# Schematic.net
KiCad netlist of a schematic drawn in EAGLE
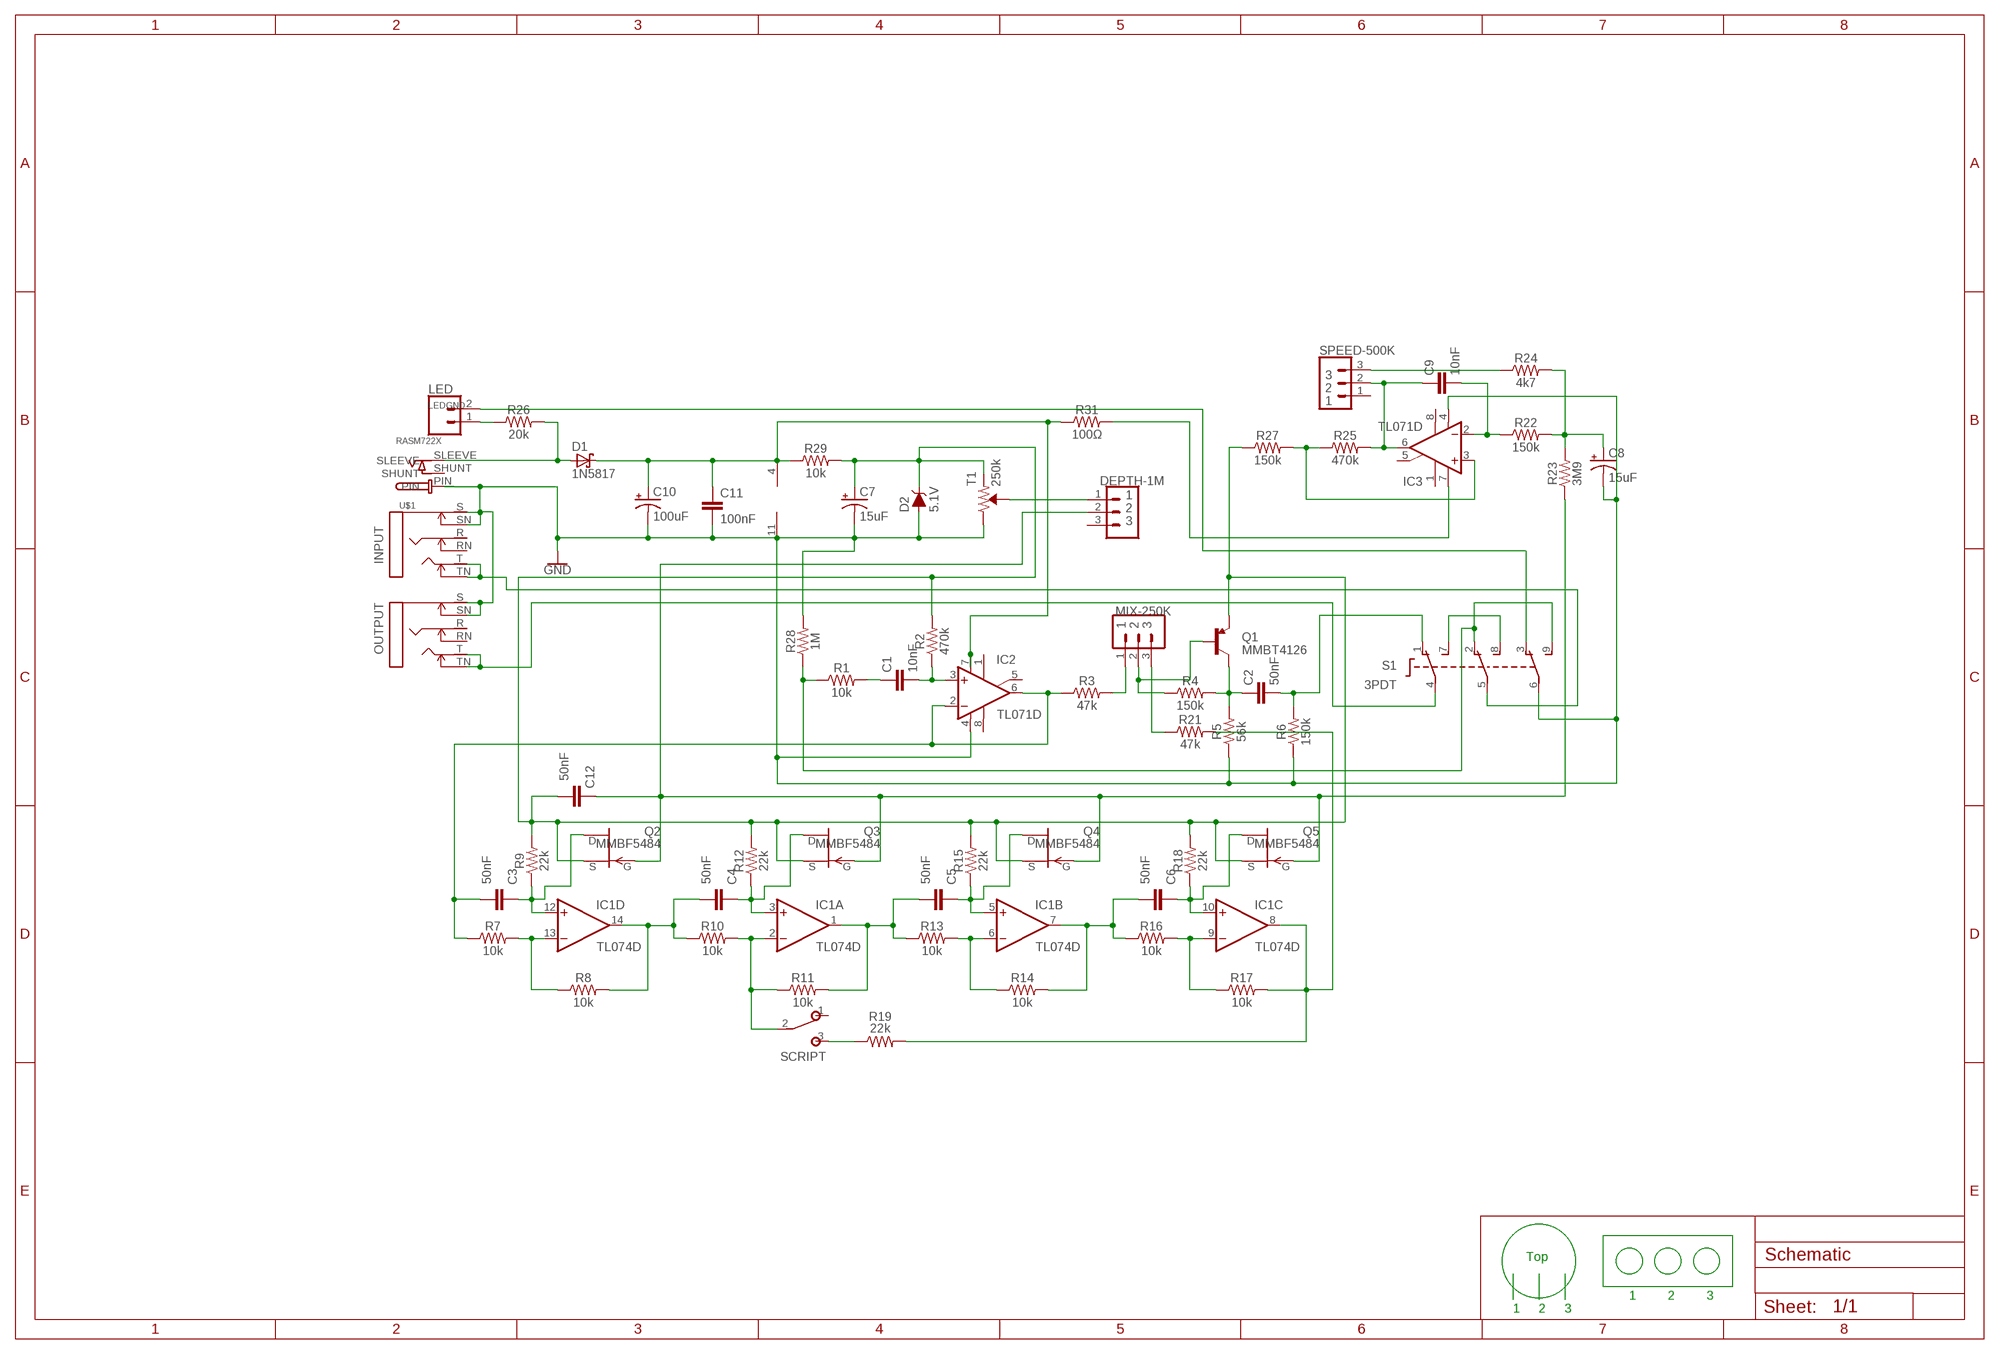
[diagram p0: schematic, sheet 1]

(export (version "E")
  (design (tool "Eeschema 10.0.6"))
  (components
    (comp (ref "C1")
      (value "10nF")
      (footprint "eagle-import:0603")
      (libsource (lib "eagle-import") (part "0.1UF-0603-25V-(+80/-20%)"))
    )
    (comp (ref "C2")
      (value "50nF")
      (footprint "eagle-import:0603")
      (libsource (lib "eagle-import") (part "0.1UF-0603-25V-(+80/-20%)"))
    )
    (comp (ref "C3")
      (value "50nF")
      (footprint "eagle-import:0603")
      (libsource (lib "eagle-import") (part "10NF-0603-50V-10%"))
    )
    (comp (ref "C4")
      (value "50nF")
      (footprint "eagle-import:0603")
      (libsource (lib "eagle-import") (part "10NF-0603-50V-10%"))
    )
    (comp (ref "C5")
      (value "50nF")
      (footprint "eagle-import:0603")
      (libsource (lib "eagle-import") (part "10NF-0603-50V-10%"))
    )
    (comp (ref "C6")
      (value "50nF")
      (footprint "eagle-import:0603")
      (libsource (lib "eagle-import") (part "10NF-0603-50V-10%"))
    )
    (comp (ref "C7")
      (value "15uF")
      (footprint "eagle-import:EIA7343")
      (libsource (lib "eagle-import") (part "100UF-POLAR-EIA7343-10V-10%(TANT)"))
    )
    (comp (ref "C8")
      (value "15uF")
      (footprint "eagle-import:EIA7343")
      (libsource (lib "eagle-import") (part "100UF-POLAR-EIA7343-10V-10%(TANT)"))
    )
    (comp (ref "C9")
      (value "10nF")
      (footprint "eagle-import:0603")
      (libsource (lib "eagle-import") (part "0.1UF-0603-25V-(+80/-20%)"))
    )
    (comp (ref "C10")
      (value "100uF")
      (footprint "eagle-import:EIA7343")
      (libsource (lib "eagle-import") (part "100UF-POLAR-EIA7343-10V-10%(TANT)"))
    )
    (comp (ref "C11")
      (value "100nF")
      (footprint "eagle-import:0603")
      (libsource (lib "eagle-import") (part "0.1UF-0603-25V-(+80/-20%)"))
    )
    (comp (ref "C12")
      (value "50nF")
      (footprint "eagle-import:0603")
      (libsource (lib "eagle-import") (part "10NF-0603-50V-10%"))
    )
    (comp (ref "D1")
      (value "1N5817")
      (footprint "eagle-import:DO41-7.6")
      (libsource (lib "eagle-import") (part "1N5817-T"))
    )
    (comp (ref "D2")
      (value "5.1V")
      (footprint "eagle-import:SOD-323")
      (libsource (lib "eagle-import") (part "DIODE-ZENER-BZT52C3V6S"))
    )
    (comp (ref "DEPTH-1M")
      (value "CONN_03")
      (footprint "eagle-import:1X03")
      (libsource (lib "eagle-import") (part "CONN_03"))
    )
    (comp (ref "IC1")
      (value "TL074D")
      (footprint "eagle-import:SO14")
      (libsource (lib "eagle-import") (part "TL074D"))
    )
    (comp (ref "IC2")
      (value "TL071D")
      (footprint "eagle-import:SO08")
      (libsource (lib "eagle-import") (part "TL071D"))
    )
    (comp (ref "IC3")
      (value "TL071D")
      (footprint "eagle-import:SO08")
      (libsource (lib "eagle-import") (part "TL071D"))
    )
    (comp (ref "INPUT")
      (value "STEREOSW")
      (footprint "eagle-import:NMJ6HCD2")
      (libsource (lib "eagle-import") (part "STEREOSW"))
    )
    (comp (ref "LED")
      (value "CONN_02")
      (footprint "eagle-import:1X02")
      (libsource (lib "eagle-import") (part "CONN_02"))
    )
    (comp (ref "MIX-250K")
      (value "CONN_03")
      (footprint "eagle-import:1X03")
      (libsource (lib "eagle-import") (part "CONN_03"))
    )
    (comp (ref "OUTPUT")
      (value "STEREOSW")
      (footprint "eagle-import:NMJ6HCD2")
      (libsource (lib "eagle-import") (part "STEREOSW"))
    )
    (comp (ref "Q1")
      (value "MMBT4126")
      (footprint "eagle-import:SOT23-3")
      (libsource (lib "eagle-import") (part "TRANSISTOR_PNPMMBT4403"))
    )
    (comp (ref "Q2")
      (value "MMBF5484")
      (footprint "eagle-import:SOT23")
      (libsource (lib "eagle-import") (part "?548SST4"))
    )
    (comp (ref "Q3")
      (value "MMBF5484")
      (footprint "eagle-import:SOT23")
      (libsource (lib "eagle-import") (part "?548SST4"))
    )
    (comp (ref "Q4")
      (value "MMBF5484")
      (footprint "eagle-import:SOT23")
      (libsource (lib "eagle-import") (part "?548SST4"))
    )
    (comp (ref "Q5")
      (value "MMBF5484")
      (footprint "eagle-import:SOT23")
      (libsource (lib "eagle-import") (part "?548SST4"))
    )
    (comp (ref "R1")
      (value "10k")
      (footprint "eagle-import:0603")
      (libsource (lib "eagle-import") (part "10KOHM-0603-1/10W-1%"))
    )
    (comp (ref "R2")
      (value "470k")
      (footprint "eagle-import:0603")
      (libsource (lib "eagle-import") (part "22KOHM-0603-1/10W-1%"))
    )
    (comp (ref "R3")
      (value "47k")
      (footprint "eagle-import:0603")
      (libsource (lib "eagle-import") (part "10KOHM-0603-1/10W-1%"))
    )
    (comp (ref "R4")
      (value "150k")
      (footprint "eagle-import:0603")
      (libsource (lib "eagle-import") (part "10KOHM-0603-1/10W-1%"))
    )
    (comp (ref "R5")
      (value "56k")
      (footprint "eagle-import:0603")
      (libsource (lib "eagle-import") (part "22KOHM-0603-1/10W-1%"))
    )
    (comp (ref "R6")
      (value "150k")
      (footprint "eagle-import:0603")
      (libsource (lib "eagle-import") (part "22KOHM-0603-1/10W-1%"))
    )
    (comp (ref "R7")
      (value "10k")
      (footprint "eagle-import:0603")
      (libsource (lib "eagle-import") (part "10KOHM-0603-1/10W-1%"))
    )
    (comp (ref "R8")
      (value "10k")
      (footprint "eagle-import:0603")
      (libsource (lib "eagle-import") (part "10KOHM-0603-1/10W-1%"))
    )
    (comp (ref "R9")
      (value "22k")
      (footprint "eagle-import:0603")
      (libsource (lib "eagle-import") (part "22KOHM-0603-1/10W-1%"))
    )
    (comp (ref "R10")
      (value "10k")
      (footprint "eagle-import:0603")
      (libsource (lib "eagle-import") (part "10KOHM-0603-1/10W-1%"))
    )
    (comp (ref "R11")
      (value "10k")
      (footprint "eagle-import:0603")
      (libsource (lib "eagle-import") (part "10KOHM-0603-1/10W-1%"))
    )
    (comp (ref "R12")
      (value "22k")
      (footprint "eagle-import:0603")
      (libsource (lib "eagle-import") (part "22KOHM-0603-1/10W-1%"))
    )
    (comp (ref "R13")
      (value "10k")
      (footprint "eagle-import:0603")
      (libsource (lib "eagle-import") (part "10KOHM-0603-1/10W-1%"))
    )
    (comp (ref "R14")
      (value "10k")
      (footprint "eagle-import:0603")
      (libsource (lib "eagle-import") (part "10KOHM-0603-1/10W-1%"))
    )
    (comp (ref "R15")
      (value "22k")
      (footprint "eagle-import:0603")
      (libsource (lib "eagle-import") (part "22KOHM-0603-1/10W-1%"))
    )
    (comp (ref "R16")
      (value "10k")
      (footprint "eagle-import:0603")
      (libsource (lib "eagle-import") (part "10KOHM-0603-1/10W-1%"))
    )
    (comp (ref "R17")
      (value "10k")
      (footprint "eagle-import:0603")
      (libsource (lib "eagle-import") (part "10KOHM-0603-1/10W-1%"))
    )
    (comp (ref "R18")
      (value "22k")
      (footprint "eagle-import:0603")
      (libsource (lib "eagle-import") (part "22KOHM-0603-1/10W-1%"))
    )
    (comp (ref "R19")
      (value "22k")
      (footprint "eagle-import:0603")
      (libsource (lib "eagle-import") (part "10KOHM-0603-1/10W-1%"))
    )
    (comp (ref "R21")
      (value "47k")
      (footprint "eagle-import:0603")
      (libsource (lib "eagle-import") (part "10KOHM-0603-1/10W-1%"))
    )
    (comp (ref "R22")
      (value "150k")
      (footprint "eagle-import:0603")
      (libsource (lib "eagle-import") (part "10KOHM-0603-1/10W-1%"))
    )
    (comp (ref "R23")
      (value "3M9")
      (footprint "eagle-import:0603")
      (libsource (lib "eagle-import") (part "10KOHM-0603-1/10W-1%"))
    )
    (comp (ref "R24")
      (value "4k7")
      (footprint "eagle-import:0603")
      (libsource (lib "eagle-import") (part "10KOHM-0603-1/10W-1%"))
    )
    (comp (ref "R25")
      (value "470k")
      (footprint "eagle-import:0603")
      (libsource (lib "eagle-import") (part "10KOHM-0603-1/10W-1%"))
    )
    (comp (ref "R26")
      (value "20k")
      (footprint "eagle-import:0603")
      (libsource (lib "eagle-import") (part "10KOHM-0603-1/10W-1%"))
    )
    (comp (ref "R27")
      (value "150k")
      (footprint "eagle-import:0603")
      (libsource (lib "eagle-import") (part "10KOHM-0603-1/10W-1%"))
    )
    (comp (ref "R28")
      (value "1M")
      (footprint "eagle-import:0603")
      (libsource (lib "eagle-import") (part "10KOHM-0603-1/10W-1%"))
    )
    (comp (ref "R29")
      (value "10k")
      (footprint "eagle-import:0603")
      (libsource (lib "eagle-import") (part "10KOHM-0603-1/10W-1%"))
    )
    (comp (ref "R31")
      (value "100Ω")
      (footprint "eagle-import:0603")
      (libsource (lib "eagle-import") (part "10KOHM-0603-1/10W-1%"))
    )
    (comp (ref "S1")
      (value "3PDT")
      (footprint "eagle-import:3PDT")
      (libsource (lib "eagle-import") (part "3PDT"))
    )
    (comp (ref "SCRIPT")
      (value "SPDT")
      (footprint "eagle-import:M9040P")
      (libsource (lib "eagle-import") (part "SPDT"))
    )
    (comp (ref "SPEED-500K")
      (value "CONN_03")
      (footprint "eagle-import:1X03")
      (libsource (lib "eagle-import") (part "CONN_03"))
    )
    (comp (ref "T1")
      (value "250k")
      (footprint "eagle-import:TRIMPOT-SMD-3MM-CLOSED")
      (libsource (lib "eagle-import") (part "TRIMPOT-SMD-3MM-CLOSED-1/8W-20%"))
    )
    (comp (ref "U$1")
      (value "RASM722X")
      (footprint "eagle-import:SWITCHCRAFT_RASM722X")
      (fields (field (name "MF") "Switchcraft"))
      (libsource (lib "eagle-import") (part "RASM722X"))
    )
  )
  (nets
    (net (code "1") (name "/1") (class "Default")
      (node (ref "MIX-250K") (pin "1") (pinfunction "1_1") (pintype "passive"))
      (node (ref "R3") (pin "2") (pinfunction "2_2") (pintype "passive"))
    )
    (net (code "2") (name "/2") (class "Default")
      (node (ref "C9") (pin "1") (pinfunction "1_1") (pintype "passive"))
      (node (ref "IC3") (pin "6") (pinfunction "OUT_6") (pintype "output"))
      (node (ref "R25") (pin "2") (pinfunction "2_2") (pintype "passive"))
      (node (ref "SPEED-500K") (pin "2") (pinfunction "2_2") (pintype "passive"))
    )
    (net (code "3") (name "/3") (class "Default")
      (node (ref "R24") (pin "1") (pinfunction "1_1") (pintype "passive"))
      (node (ref "SPEED-500K") (pin "3") (pinfunction "3_3") (pintype "passive"))
    )
    (net (code "4") (name "/LEDGND") (class "Default")
      (node (ref "LED") (pin "2") (pinfunction "2_2") (pintype "passive"))
      (node (ref "S1") (pin "3") (pinfunction "O3_3") (pintype "passive"))
    )
    (net (code "6") (name "/SHUNT") (class "Default")
      (node (ref "U$1") (pin "SHUNT") (pinfunction "SHUNT_SHUNT") (pintype "power_in"))
    )
    (net (code "7") (name "GND") (class "Default")
      (node (ref "C10") (pin "C") (pinfunction "-_C") (pintype "passive"))
      (node (ref "C11") (pin "2") (pinfunction "2_2") (pintype "passive"))
      (node (ref "C7") (pin "C") (pinfunction "-_C") (pintype "passive"))
      (node (ref "C8") (pin "C") (pinfunction "-_C") (pintype "passive"))
      (node (ref "D2") (pin "A") (pinfunction "A_A") (pintype "passive"))
      (node (ref "IC1") (pin "11") (pinfunction "V-_11") (pintype "power_in"))
      (node (ref "IC2") (pin "4") (pinfunction "V-_4") (pintype "power_in"))
      (node (ref "IC3") (pin "4") (pinfunction "V-_4") (pintype "power_in"))
      (node (ref "INPUT") (pin "S") (pinfunction "S_S") (pintype "passive"))
      (node (ref "INPUT") (pin "SN") (pinfunction "SN_SN") (pintype "passive"))
      (node (ref "OUTPUT") (pin "S") (pinfunction "S_S") (pintype "passive"))
      (node (ref "OUTPUT") (pin "SN") (pinfunction "SN_SN") (pintype "passive"))
      (node (ref "R28") (pin "2") (pinfunction "2_2") (pintype "passive"))
      (node (ref "R5") (pin "1") (pinfunction "1_1") (pintype "passive"))
      (node (ref "R6") (pin "1") (pinfunction "1_1") (pintype "passive"))
      (node (ref "S1") (pin "6") (pinfunction "P3_6") (pintype "passive"))
      (node (ref "T1") (pin "3") (pinfunction "CW_3") (pintype "passive"))
      (node (ref "U$1") (pin "PIN") (pinfunction "PIN_PIN") (pintype "bidirectional"))
    )
    (net (code "8") (name "Net-(C1-Pad1)") (class "Default")
      (node (ref "C1") (pin "1") (pinfunction "1_1") (pintype "passive"))
      (node (ref "R1") (pin "2") (pinfunction "2_2") (pintype "passive"))
    )
    (net (code "9") (name "Net-(C7-+)") (class "Default")
      (node (ref "C12") (pin "2") (pinfunction "2_2") (pintype "passive"))
      (node (ref "C7") (pin "A") (pinfunction "+_A") (pintype "passive"))
      (node (ref "D2") (pin "C") (pinfunction "C_C") (pintype "passive"))
      (node (ref "Q1") (pin "2") (pinfunction "E_2") (pintype "passive"))
      (node (ref "Q2") (pin "2") (pinfunction "S_2") (pintype "passive"))
      (node (ref "Q3") (pin "2") (pinfunction "S_2") (pintype "passive"))
      (node (ref "Q4") (pin "2") (pinfunction "S_2") (pintype "passive"))
      (node (ref "Q5") (pin "2") (pinfunction "S_2") (pintype "passive"))
      (node (ref "R12") (pin "2") (pinfunction "2_2") (pintype "passive"))
      (node (ref "R15") (pin "2") (pinfunction "2_2") (pintype "passive"))
      (node (ref "R18") (pin "2") (pinfunction "2_2") (pintype "passive"))
      (node (ref "R2") (pin "2") (pinfunction "2_2") (pintype "passive"))
      (node (ref "R27") (pin "1") (pinfunction "1_1") (pintype "passive"))
      (node (ref "R29") (pin "2") (pinfunction "2_2") (pintype "passive"))
      (node (ref "R9") (pin "2") (pinfunction "2_2") (pintype "passive"))
      (node (ref "T1") (pin "1") (pinfunction "CCW_1") (pintype "passive"))
    )
    (net (code "10") (name "Net-(C8-+)") (class "Default")
      (node (ref "C8") (pin "A") (pinfunction "+_A") (pintype "passive"))
      (node (ref "R22") (pin "2") (pinfunction "2_2") (pintype "passive"))
      (node (ref "R23") (pin "2") (pinfunction "2_2") (pintype "passive"))
      (node (ref "R24") (pin "2") (pinfunction "2_2") (pintype "passive"))
    )
    (net (code "11") (name "Net-(C10-+)") (class "Default")
      (node (ref "C10") (pin "A") (pinfunction "+_A") (pintype "passive"))
      (node (ref "C11") (pin "1") (pinfunction "1_1") (pintype "passive"))
      (node (ref "D1") (pin "C") (pinfunction "C_C") (pintype "passive"))
      (node (ref "IC1") (pin "4") (pinfunction "V+_4") (pintype "power_in"))
      (node (ref "IC2") (pin "7") (pinfunction "V+_7") (pintype "power_in"))
      (node (ref "R29") (pin "1") (pinfunction "1_1") (pintype "passive"))
      (node (ref "R31") (pin "1") (pinfunction "1_1") (pintype "passive"))
    )
    (net (code "12") (name "Net-(D1-PadA)") (class "Default")
      (node (ref "D1") (pin "A") (pinfunction "A_A") (pintype "passive"))
      (node (ref "R26") (pin "2") (pinfunction "2_2") (pintype "passive"))
      (node (ref "U$1") (pin "SLEEVE") (pinfunction "SLEEVE_SLEEVE") (pintype "power_in"))
    )
    (net (code "13") (name "Net-(IC1A-+IN)") (class "Default")
      (node (ref "C4") (pin "1") (pinfunction "1_1") (pintype "passive"))
      (node (ref "IC1") (pin "3") (pinfunction "+IN_3") (pintype "input"))
      (node (ref "Q3") (pin "1") (pinfunction "D_1") (pintype "passive"))
      (node (ref "R12") (pin "1") (pinfunction "1_1") (pintype "passive"))
    )
    (net (code "14") (name "Net-(IC1A--IN)") (class "Default")
      (node (ref "IC1") (pin "2") (pinfunction "-IN_2") (pintype "input"))
      (node (ref "R10") (pin "2") (pinfunction "2_2") (pintype "passive"))
      (node (ref "R11") (pin "1") (pinfunction "1_1") (pintype "passive"))
      (node (ref "SCRIPT") (pin "2") (pinfunction "P_2") (pintype "passive"))
    )
    (net (code "15") (name "Net-(IC1A-OUT)") (class "Default")
      (node (ref "C5") (pin "2") (pinfunction "2_2") (pintype "passive"))
      (node (ref "IC1") (pin "1") (pinfunction "OUT_1") (pintype "output"))
      (node (ref "R11") (pin "2") (pinfunction "2_2") (pintype "passive"))
      (node (ref "R13") (pin "1") (pinfunction "1_1") (pintype "passive"))
    )
    (net (code "16") (name "Net-(IC1B-+IN)") (class "Default")
      (node (ref "C5") (pin "1") (pinfunction "1_1") (pintype "passive"))
      (node (ref "IC1") (pin "5") (pinfunction "+IN_5") (pintype "input"))
      (node (ref "Q4") (pin "1") (pinfunction "D_1") (pintype "passive"))
      (node (ref "R15") (pin "1") (pinfunction "1_1") (pintype "passive"))
    )
    (net (code "17") (name "Net-(IC1B--IN)") (class "Default")
      (node (ref "IC1") (pin "6") (pinfunction "-IN_6") (pintype "input"))
      (node (ref "R13") (pin "2") (pinfunction "2_2") (pintype "passive"))
      (node (ref "R14") (pin "1") (pinfunction "1_1") (pintype "passive"))
    )
    (net (code "18") (name "Net-(IC1B-OUT)") (class "Default")
      (node (ref "C6") (pin "2") (pinfunction "2_2") (pintype "passive"))
      (node (ref "IC1") (pin "7") (pinfunction "OUT_7") (pintype "output"))
      (node (ref "R14") (pin "2") (pinfunction "2_2") (pintype "passive"))
      (node (ref "R16") (pin "1") (pinfunction "1_1") (pintype "passive"))
    )
    (net (code "19") (name "Net-(IC1C-+IN)") (class "Default")
      (node (ref "C6") (pin "1") (pinfunction "1_1") (pintype "passive"))
      (node (ref "IC1") (pin "10") (pinfunction "+IN_10") (pintype "input"))
      (node (ref "Q5") (pin "1") (pinfunction "D_1") (pintype "passive"))
      (node (ref "R18") (pin "1") (pinfunction "1_1") (pintype "passive"))
    )
    (net (code "20") (name "Net-(IC1C--IN)") (class "Default")
      (node (ref "IC1") (pin "9") (pinfunction "-IN_9") (pintype "input"))
      (node (ref "R16") (pin "2") (pinfunction "2_2") (pintype "passive"))
      (node (ref "R17") (pin "1") (pinfunction "1_1") (pintype "passive"))
    )
    (net (code "21") (name "Net-(IC1C-OUT)") (class "Default")
      (node (ref "IC1") (pin "8") (pinfunction "OUT_8") (pintype "output"))
      (node (ref "R17") (pin "2") (pinfunction "2_2") (pintype "passive"))
      (node (ref "R19") (pin "2") (pinfunction "2_2") (pintype "passive"))
      (node (ref "R21") (pin "2") (pinfunction "2_2") (pintype "passive"))
    )
    (net (code "22") (name "Net-(IC1D-+IN)") (class "Default")
      (node (ref "C3") (pin "1") (pinfunction "1_1") (pintype "passive"))
      (node (ref "IC1") (pin "12") (pinfunction "+IN_12") (pintype "input"))
      (node (ref "Q2") (pin "1") (pinfunction "D_1") (pintype "passive"))
      (node (ref "R9") (pin "1") (pinfunction "1_1") (pintype "passive"))
    )
    (net (code "23") (name "Net-(IC1D--IN)") (class "Default")
      (node (ref "IC1") (pin "13") (pinfunction "-IN_13") (pintype "input"))
      (node (ref "R7") (pin "2") (pinfunction "2_2") (pintype "passive"))
      (node (ref "R8") (pin "1") (pinfunction "1_1") (pintype "passive"))
    )
    (net (code "24") (name "Net-(IC1D-OUT)") (class "Default")
      (node (ref "C4") (pin "2") (pinfunction "2_2") (pintype "passive"))
      (node (ref "IC1") (pin "14") (pinfunction "OUT_14") (pintype "output"))
      (node (ref "R10") (pin "1") (pinfunction "1_1") (pintype "passive"))
      (node (ref "R8") (pin "2") (pinfunction "2_2") (pintype "passive"))
    )
    (net (code "25") (name "Net-(IC2-+IN)") (class "Default")
      (node (ref "C1") (pin "2") (pinfunction "2_2") (pintype "passive"))
      (node (ref "IC2") (pin "3") (pinfunction "+IN_3") (pintype "input"))
      (node (ref "R2") (pin "1") (pinfunction "1_1") (pintype "passive"))
    )
    (net (code "26") (name "Net-(IC2--IN)") (class "Default")
      (node (ref "C3") (pin "2") (pinfunction "2_2") (pintype "passive"))
      (node (ref "IC2") (pin "2") (pinfunction "-IN_2") (pintype "input"))
      (node (ref "IC2") (pin "6") (pinfunction "OUT_6") (pintype "output"))
      (node (ref "R3") (pin "1") (pinfunction "1_1") (pintype "passive"))
      (node (ref "R7") (pin "1") (pinfunction "1_1") (pintype "passive"))
    )
    (net (code "27") (name "Net-(IC3-+IN)") (class "Default")
      (node (ref "IC3") (pin "3") (pinfunction "+IN_3") (pintype "input"))
      (node (ref "R25") (pin "1") (pinfunction "1_1") (pintype "passive"))
      (node (ref "R27") (pin "2") (pinfunction "2_2") (pintype "passive"))
    )
    (net (code "28") (name "Net-(IC3--IN)") (class "Default")
      (node (ref "C9") (pin "2") (pinfunction "2_2") (pintype "passive"))
      (node (ref "IC3") (pin "2") (pinfunction "-IN_2") (pintype "input"))
      (node (ref "R22") (pin "1") (pinfunction "1_1") (pintype "passive"))
    )
    (net (code "29") (name "Net-(IC3-V+)") (class "Default")
      (node (ref "IC3") (pin "7") (pinfunction "V+_7") (pintype "power_in"))
      (node (ref "R31") (pin "2") (pinfunction "2_2") (pintype "passive"))
    )
    (net (code "30") (name "Net-(LED-Pad1)") (class "Default")
      (node (ref "LED") (pin "1") (pinfunction "1_1") (pintype "passive"))
      (node (ref "R26") (pin "1") (pinfunction "1_1") (pintype "passive"))
    )
    (net (code "31") (name "Net-(MIX-250K-Pad3)") (class "Default")
      (node (ref "MIX-250K") (pin "3") (pinfunction "3_3") (pintype "passive"))
      (node (ref "R21") (pin "1") (pinfunction "1_1") (pintype "passive"))
    )
    (net (code "32") (name "Net-(Q1-B)") (class "Default")
      (node (ref "MIX-250K") (pin "2") (pinfunction "2_2") (pintype "passive"))
      (node (ref "Q1") (pin "1") (pinfunction "B_1") (pintype "passive"))
      (node (ref "R4") (pin "1") (pinfunction "1_1") (pintype "passive"))
    )
    (net (code "33") (name "Net-(Q1-C)") (class "Default")
      (node (ref "C2") (pin "1") (pinfunction "1_1") (pintype "passive"))
      (node (ref "Q1") (pin "3") (pinfunction "C_3") (pintype "passive"))
      (node (ref "R4") (pin "2") (pinfunction "2_2") (pintype "passive"))
      (node (ref "R5") (pin "2") (pinfunction "2_2") (pintype "passive"))
    )
    (net (code "34") (name "Net-(Q2-G)") (class "Default")
      (node (ref "C12") (pin "1") (pinfunction "1_1") (pintype "passive"))
      (node (ref "DEPTH-1M") (pin "2") (pinfunction "2_2") (pintype "passive"))
      (node (ref "Q2") (pin "3") (pinfunction "G_3") (pintype "passive"))
      (node (ref "Q3") (pin "3") (pinfunction "G_3") (pintype "passive"))
      (node (ref "Q4") (pin "3") (pinfunction "G_3") (pintype "passive"))
      (node (ref "Q5") (pin "3") (pinfunction "G_3") (pintype "passive"))
      (node (ref "R23") (pin "1") (pinfunction "1_1") (pintype "passive"))
    )
    (net (code "35") (name "Net-(S1-O1)") (class "Default")
      (node (ref "C2") (pin "2") (pinfunction "2_2") (pintype "passive"))
      (node (ref "R6") (pin "2") (pinfunction "2_2") (pintype "passive"))
      (node (ref "S1") (pin "1") (pinfunction "O1_1") (pintype "passive"))
    )
    (net (code "36") (name "Net-(S1-O2)") (class "Default")
      (node (ref "R1") (pin "1") (pinfunction "1_1") (pintype "passive"))
      (node (ref "R28") (pin "1") (pinfunction "1_1") (pintype "passive"))
      (node (ref "S1") (pin "2") (pinfunction "O2_2") (pintype "passive"))
      (node (ref "S1") (pin "9") (pinfunction "S3_9") (pintype "passive"))
    )
    (net (code "37") (name "Net-(S1-P1)") (class "Default")
      (node (ref "OUTPUT") (pin "T") (pinfunction "T_T") (pintype "passive"))
      (node (ref "OUTPUT") (pin "TN") (pinfunction "TN_TN") (pintype "passive"))
      (node (ref "S1") (pin "4") (pinfunction "P1_4") (pintype "passive"))
    )
    (net (code "38") (name "Net-(S1-P2)") (class "Default")
      (node (ref "INPUT") (pin "T") (pinfunction "T_T") (pintype "passive"))
      (node (ref "INPUT") (pin "TN") (pinfunction "TN_TN") (pintype "passive"))
      (node (ref "S1") (pin "5") (pinfunction "P2_5") (pintype "passive"))
    )
    (net (code "39") (name "Net-(S1-S1)") (class "Default")
      (node (ref "S1") (pin "7") (pinfunction "S1_7") (pintype "passive"))
      (node (ref "S1") (pin "8") (pinfunction "S2_8") (pintype "passive"))
    )
    (net (code "40") (name "Net-(SCRIPT-S)") (class "Default")
      (node (ref "R19") (pin "1") (pinfunction "1_1") (pintype "passive"))
      (node (ref "SCRIPT") (pin "3") (pinfunction "S_3") (pintype "passive"))
    )
    (net (code "41") (name "Net-(T1-WIPER)") (class "Default")
      (node (ref "DEPTH-1M") (pin "1") (pinfunction "1_1") (pintype "passive"))
      (node (ref "T1") (pin "2") (pinfunction "WIPER_2") (pintype "passive"))
    )
    (net (code "42") (name "unconnected-(DEPTH-1M-Pad3)") (class "Default")
      (node (ref "DEPTH-1M") (pin "3") (pinfunction "3_3") (pintype "passive"))
    )
    (net (code "43") (name "unconnected-(IC2-ON1-Pad1)") (class "Default")
      (node (ref "IC2") (pin "1") (pinfunction "ON1_1") (pintype "passive"))
    )
    (net (code "44") (name "unconnected-(IC2-ON2-Pad5)") (class "Default")
      (node (ref "IC2") (pin "5") (pinfunction "ON2_5") (pintype "passive"))
    )
    (net (code "45") (name "unconnected-(IC2-OPT-Pad8)") (class "Default")
      (node (ref "IC2") (pin "8") (pinfunction "OPT_8") (pintype "passive"))
    )
    (net (code "46") (name "unconnected-(IC3-ON1-Pad1)") (class "Default")
      (node (ref "IC3") (pin "1") (pinfunction "ON1_1") (pintype "passive"))
    )
    (net (code "47") (name "unconnected-(IC3-ON2-Pad5)") (class "Default")
      (node (ref "IC3") (pin "5") (pinfunction "ON2_5") (pintype "passive"))
    )
    (net (code "48") (name "unconnected-(IC3-OPT-Pad8)") (class "Default")
      (node (ref "IC3") (pin "8") (pinfunction "OPT_8") (pintype "passive"))
    )
    (net (code "49") (name "unconnected-(INPUT-PadR)") (class "Default")
      (node (ref "INPUT") (pin "R") (pinfunction "R_R") (pintype "passive"))
    )
    (net (code "50") (name "unconnected-(INPUT-PadRN)") (class "Default")
      (node (ref "INPUT") (pin "RN") (pinfunction "RN_RN") (pintype "passive"))
    )
    (net (code "51") (name "unconnected-(OUTPUT-PadR)") (class "Default")
      (node (ref "OUTPUT") (pin "R") (pinfunction "R_R") (pintype "passive"))
    )
    (net (code "52") (name "unconnected-(OUTPUT-PadRN)") (class "Default")
      (node (ref "OUTPUT") (pin "RN") (pinfunction "RN_RN") (pintype "passive"))
    )
    (net (code "53") (name "unconnected-(SCRIPT-O-Pad1)") (class "Default")
      (node (ref "SCRIPT") (pin "1") (pinfunction "O_1") (pintype "passive"))
    )
    (net (code "54") (name "unconnected-(SPEED-500K-Pad1)") (class "Default")
      (node (ref "SPEED-500K") (pin "1") (pinfunction "1_1") (pintype "passive"))
    )
  )
)
